# Estacion_meteo.net
KiCad netlist of a schematic drawn in EasyEDA
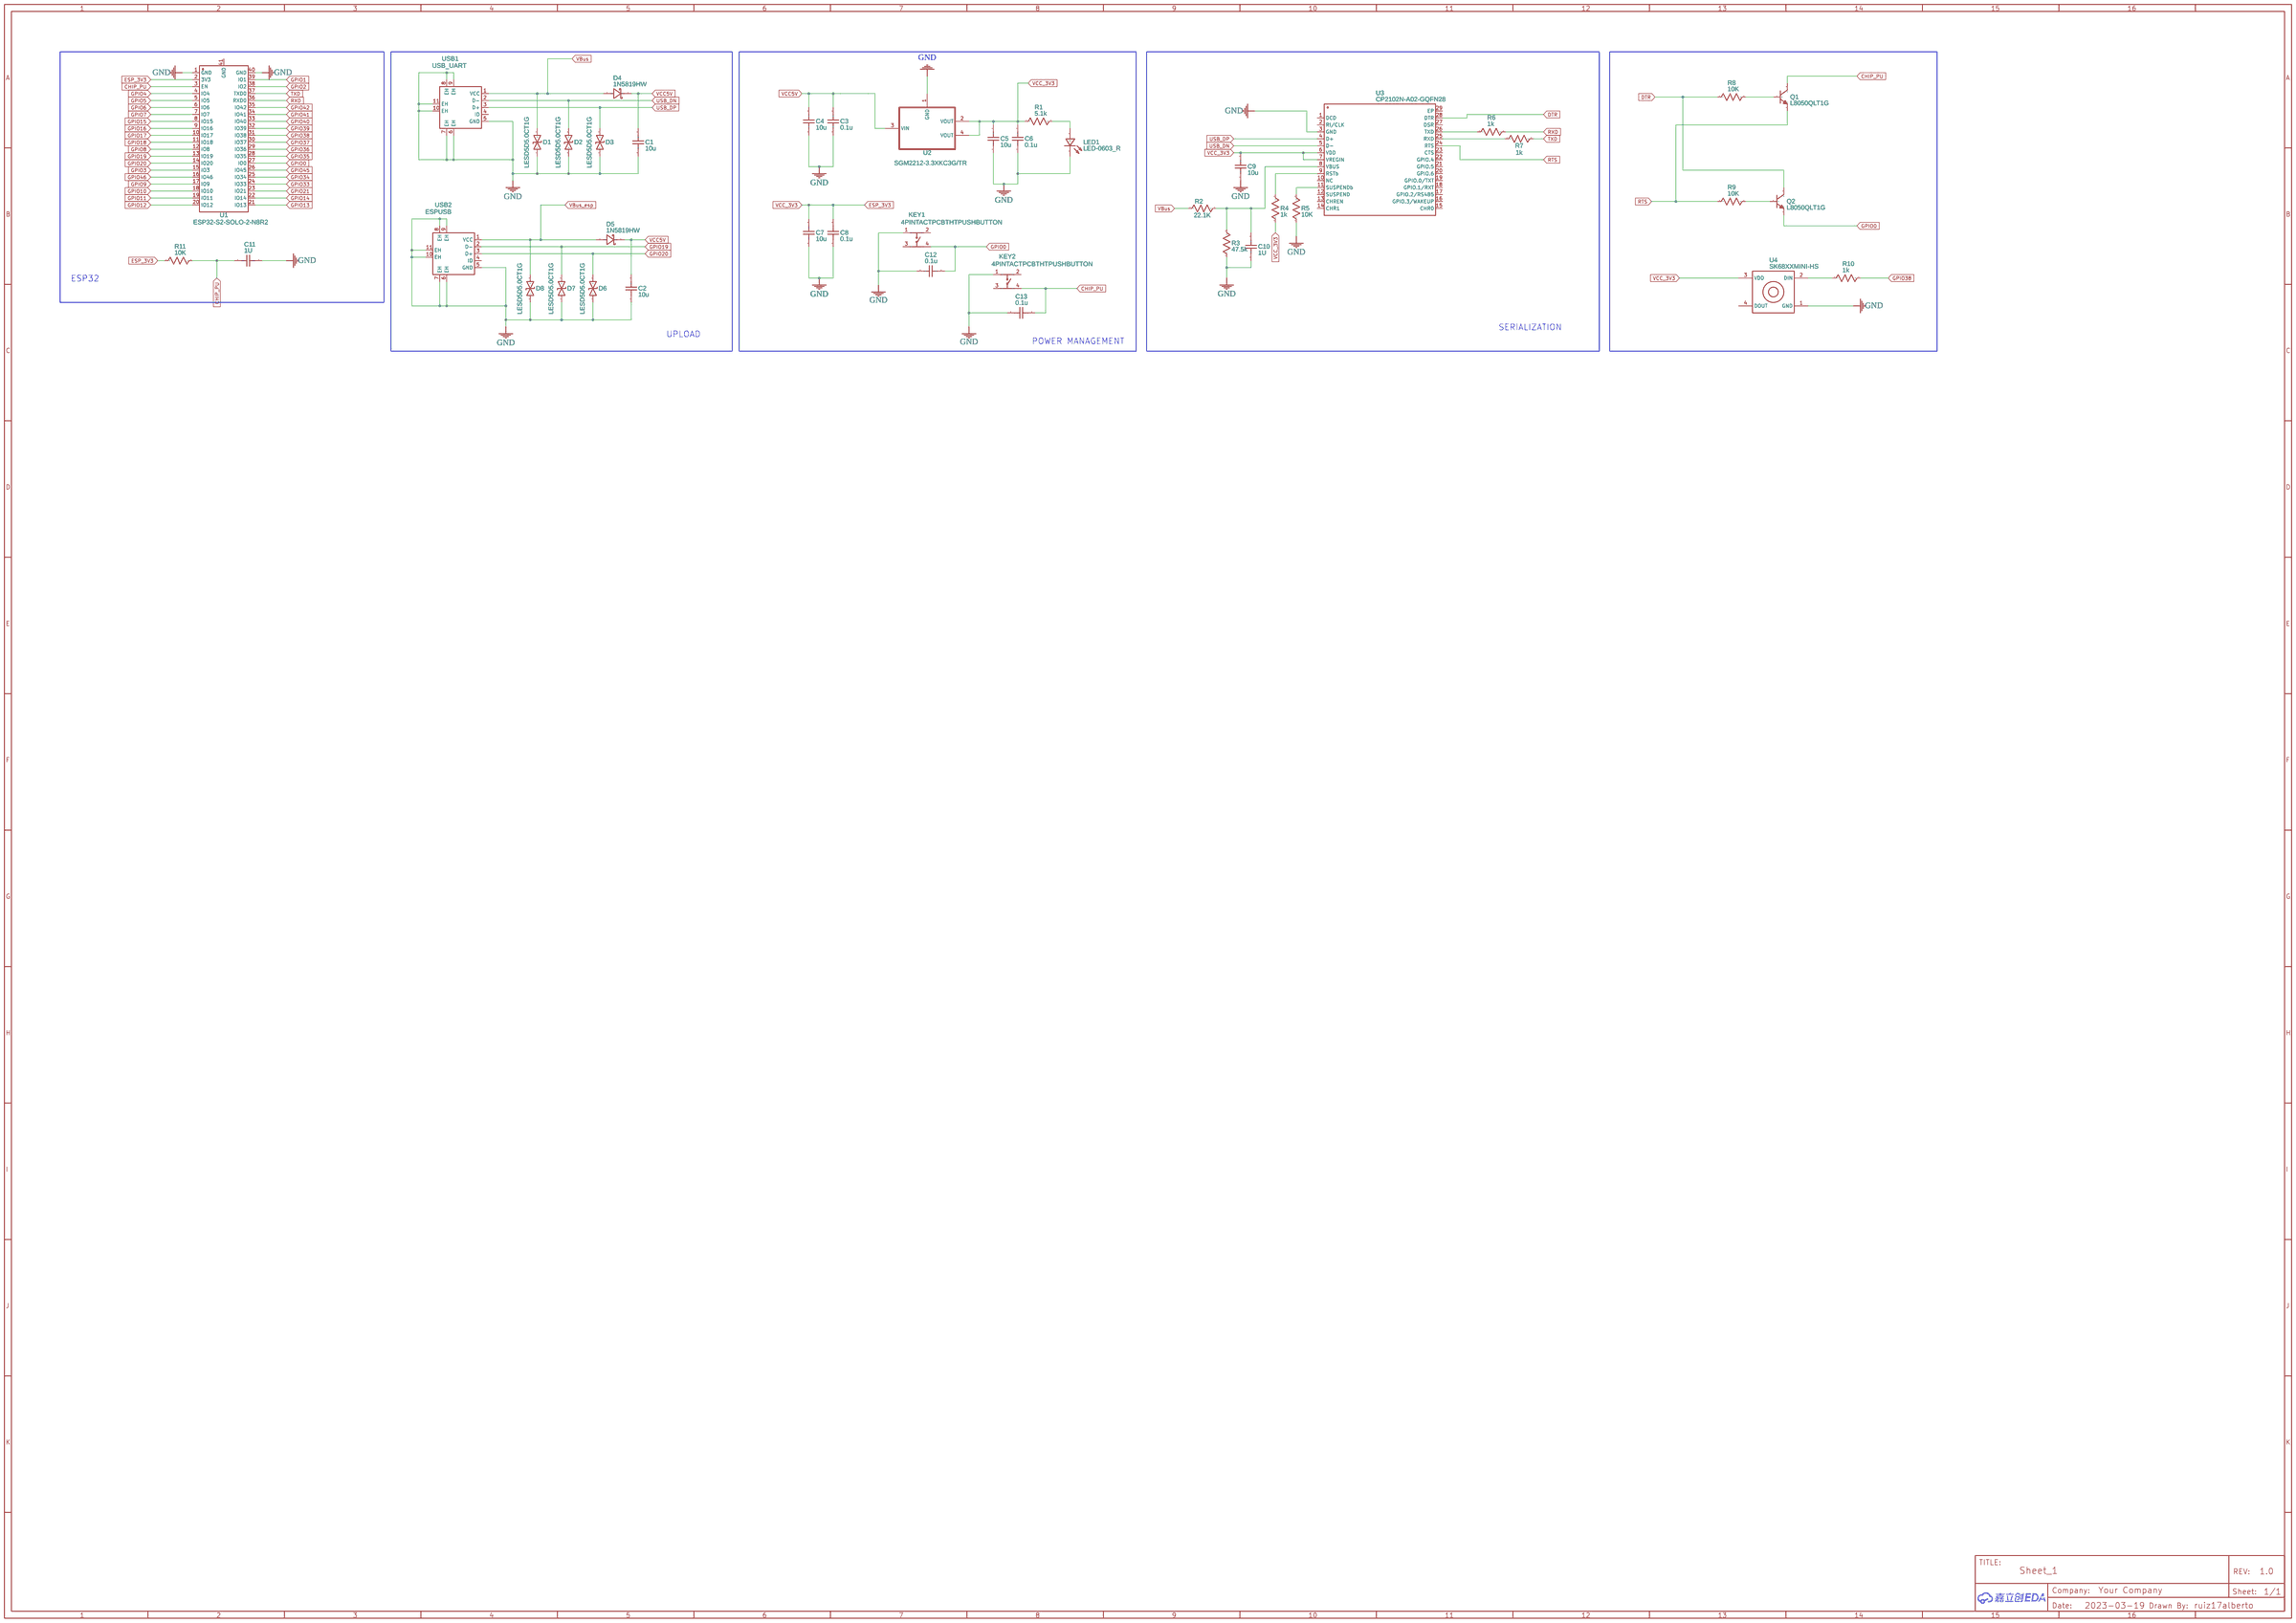
[diagram p0: schematic sheet]

(export (version "E")
  (design (tool "Eeschema 10.0.6"))
  (components
    (comp (ref "C1") (value "10u") (libsource (lib "") (part "C_0603_US")))
    (comp (ref "C2") (value "10u") (libsource (lib "") (part "C_0603_US")))
    (comp (ref "C3") (value "0.1u") (libsource (lib "") (part "C_0603_US")))
    (comp (ref "C4") (value "10u") (libsource (lib "") (part "C_0603_US")))
    (comp (ref "C5") (value "10u") (libsource (lib "") (part "C_0603_US")))
    (comp (ref "C6") (value "0.1u") (libsource (lib "") (part "C_0603_US")))
    (comp (ref "C7") (value "10u") (libsource (lib "") (part "C_0603_US")))
    (comp (ref "C8") (value "0.1u") (libsource (lib "") (part "C_0603_US")))
    (comp (ref "C9") (value "10u") (libsource (lib "") (part "C_0603_US")))
    (comp (ref "C10") (value "1U") (libsource (lib "") (part "C_0603_US")))
    (comp (ref "C11") (value "1U") (libsource (lib "") (part "C_0603_US_2")))
    (comp (ref "C12") (value "0.1u") (libsource (lib "") (part "C_0603_US_1")))
    (comp (ref "C13") (value "0.1u") (libsource (lib "") (part "C_0603_US_1")))
    (comp (ref "D1")
      (value "LESD5D5.0CT1G")
      (fields (field (name "Manufacturer") "LRC(乐山无线电)"))
      (libsource (lib "") (part "LESD5D5.0CT1G"))
    )
    (comp (ref "D2")
      (value "LESD5D5.0CT1G")
      (fields (field (name "Manufacturer") "LRC(乐山无线电)"))
      (libsource (lib "") (part "LESD5D5.0CT1G"))
    )
    (comp (ref "D3")
      (value "LESD5D5.0CT1G")
      (fields (field (name "Manufacturer") "LRC(乐山无线电)"))
      (libsource (lib "") (part "LESD5D5.0CT1G"))
    )
    (comp (ref "D4")
      (value "1N5819HW")
      (fields (field (name "Manufacturer") "TECH PUBLIC(台舟)"))
      (libsource (lib "") (part "1N5819HW"))
    )
    (comp (ref "D5")
      (value "1N5819HW")
      (fields (field (name "Manufacturer") "TECH PUBLIC(台舟)"))
      (libsource (lib "") (part "1N5819HW"))
    )
    (comp (ref "D6")
      (value "LESD5D5.0CT1G")
      (fields (field (name "Manufacturer") "LRC(乐山无线电)"))
      (libsource (lib "") (part "LESD5D5.0CT1G"))
    )
    (comp (ref "D7")
      (value "LESD5D5.0CT1G")
      (fields (field (name "Manufacturer") "LRC(乐山无线电)"))
      (libsource (lib "") (part "LESD5D5.0CT1G"))
    )
    (comp (ref "D8")
      (value "LESD5D5.0CT1G")
      (fields (field (name "Manufacturer") "LRC(乐山无线电)"))
      (libsource (lib "") (part "LESD5D5.0CT1G"))
    )
    (comp (ref "KEY1")
      (value "4PINTACTPCBTHTPUSHBUTTON")
      (fields (field (name "Manufacturer Part") "4pinTACTPCBTHTPushButton"))
      (libsource (lib "") (part "4PINTACTPCBTHTPUSHBUTTON"))
    )
    (comp (ref "KEY2")
      (value "4PINTACTPCBTHTPUSHBUTTON")
      (fields (field (name "Manufacturer Part") "4pinTACTPCBTHTPushButton"))
      (libsource (lib "") (part "4PINTACTPCBTHTPUSHBUTTON"))
    )
    (comp (ref "LED1")
      (value "LED-0603_R")
      (fields
        (field (name "BOM_Manufacturer Part") "19-217/R6C-AL1M2VY/3T")
        (field (name "BOM_Supplier Part") "C72044")
      )
      (libsource (lib "") (part "LED-0603_R"))
    )
    (comp (ref "Q1")
      (value "L8050QLT1G")
      (fields (field (name "Manufacturer") "LRC(乐山无线电)"))
      (libsource (lib "") (part "L8050QLT1G"))
    )
    (comp (ref "Q2")
      (value "L8050QLT1G")
      (fields (field (name "Manufacturer") "LRC(乐山无线电)"))
      (libsource (lib "") (part "L8050QLT1G"))
    )
    (comp (ref "R1") (value "5.1k") (libsource (lib "") (part "R_0603_US")))
    (comp (ref "R2") (value "22.1K") (libsource (lib "") (part "R_0603_US")))
    (comp (ref "R3") (value "47.5k") (libsource (lib "") (part "R_0603_US_1")))
    (comp (ref "R4") (value "1k") (libsource (lib "") (part "R_0603_US_1")))
    (comp (ref "R5") (value "10K") (libsource (lib "") (part "R_0603_US_1")))
    (comp (ref "R6") (value "1k") (libsource (lib "") (part "R_0603_US")))
    (comp (ref "R7") (value "1k") (libsource (lib "") (part "R_0603_US")))
    (comp (ref "R8") (value "10K") (libsource (lib "") (part "R_0603_US")))
    (comp (ref "R9") (value "10K") (libsource (lib "") (part "R_0603_US")))
    (comp (ref "R10") (value "1k") (libsource (lib "") (part "R_0603_US")))
    (comp (ref "R11") (value "10K") (libsource (lib "") (part "R_0603_US")))
    (comp (ref "U1") (value "ESP32-S2-SOLO-2-N8R2") (libsource (lib "") (part "ESP32-S2-SOLO-2-N8R2")))
    (comp (ref "U2") (value "SGM2212-3.3XKC3G/TR") (libsource (lib "") (part "SGM2212-3.3XKC3G/TR")))
    (comp (ref "U3")
      (value "CP2102N-A02-GQFN28")
      (fields (field (name "Manufacturer") "SKYWORKS/SILICON LABS(芯科)"))
      (libsource (lib "") (part "CP2102N-A02-GQFN28"))
    )
    (comp (ref "U4")
      (value "SK68XXMINI-HS")
      (fields (field (name "BOM_Supplier Part") "1528-1541-ND"))
      (libsource (lib "") (part "SK68XXMINI-HS"))
    )
    (comp (ref "USB1")
      (value "USB_UART")
      (fields (field (name "Manufacturer Part") "MICROUSB5S"))
      (libsource (lib "") (part "MICROUSB5S"))
    )
    (comp (ref "USB2")
      (value "ESPUSB")
      (fields (field (name "Manufacturer Part") "MICROUSB5S"))
      (libsource (lib "") (part "MICROUSB5S"))
    )
  )
  (nets
    (net (code "1") (name "CHIP_PU") (class "Default")
      (node (ref "C11") (pin "1") (pinfunction "1_1") (pintype "unspecified"))
      (node (ref "C13") (pin "1") (pinfunction "1_1") (pintype "unspecified"))
      (node (ref "KEY2") (pin "4") (pinfunction "4_4") (pintype "unspecified"))
      (node (ref "Q1") (pin "3") (pinfunction "C_3") (pintype "unspecified"))
      (node (ref "R11") (pin "2") (pinfunction "2_2") (pintype "unspecified"))
      (node (ref "U1") (pin "3") (pinfunction "EN_3") (pintype "unspecified"))
    )
    (net (code "2") (name "DTR") (class "Default")
      (node (ref "Q2") (pin "3") (pinfunction "C_3") (pintype "unspecified"))
      (node (ref "R8") (pin "1") (pinfunction "1_1") (pintype "unspecified"))
      (node (ref "U3") (pin "28") (pinfunction "DTR_28") (pintype "unspecified"))
    )
    (net (code "3") (name "ESP_3V3") (class "Default")
      (node (ref "C5") (pin "2") (pinfunction "2_2") (pintype "unspecified"))
      (node (ref "C6") (pin "2") (pinfunction "2_2") (pintype "unspecified"))
      (node (ref "C7") (pin "2") (pinfunction "2_2") (pintype "unspecified"))
      (node (ref "C8") (pin "2") (pinfunction "2_2") (pintype "unspecified"))
      (node (ref "C9") (pin "2") (pinfunction "2_2") (pintype "unspecified"))
      (node (ref "R1") (pin "1") (pinfunction "1_1") (pintype "unspecified"))
      (node (ref "R11") (pin "1") (pinfunction "1_1") (pintype "unspecified"))
      (node (ref "R4") (pin "1") (pinfunction "1_1") (pintype "unspecified"))
      (node (ref "U1") (pin "2") (pinfunction "3V3_2") (pintype "unspecified"))
      (node (ref "U2") (pin "2") (pinfunction "VOUT_2") (pintype "unspecified"))
      (node (ref "U2") (pin "4") (pinfunction "VOUT_4") (pintype "unspecified"))
      (node (ref "U3") (pin "6") (pinfunction "VDD_6") (pintype "unspecified"))
      (node (ref "U3") (pin "7") (pinfunction "VREGIN_7") (pintype "unspecified"))
      (node (ref "U4") (pin "3") (pinfunction "VDD_3") (pintype "unspecified"))
    )
    (net (code "4") (name "GND") (class "Default")
      (node (ref "C1") (pin "1") (pinfunction "1_1") (pintype "unspecified"))
      (node (ref "C10") (pin "1") (pinfunction "1_1") (pintype "unspecified"))
      (node (ref "C11") (pin "2") (pinfunction "2_2") (pintype "unspecified"))
      (node (ref "C12") (pin "2") (pinfunction "2_2") (pintype "unspecified"))
      (node (ref "C13") (pin "2") (pinfunction "2_2") (pintype "unspecified"))
      (node (ref "C2") (pin "1") (pinfunction "1_1") (pintype "unspecified"))
      (node (ref "C3") (pin "1") (pinfunction "1_1") (pintype "unspecified"))
      (node (ref "C4") (pin "1") (pinfunction "1_1") (pintype "unspecified"))
      (node (ref "C5") (pin "1") (pinfunction "1_1") (pintype "unspecified"))
      (node (ref "C6") (pin "1") (pinfunction "1_1") (pintype "unspecified"))
      (node (ref "C7") (pin "1") (pinfunction "1_1") (pintype "unspecified"))
      (node (ref "C8") (pin "1") (pinfunction "1_1") (pintype "unspecified"))
      (node (ref "C9") (pin "1") (pinfunction "1_1") (pintype "unspecified"))
      (node (ref "D1") (pin "1") (pinfunction "1_1") (pintype "unspecified"))
      (node (ref "D2") (pin "1") (pinfunction "1_1") (pintype "unspecified"))
      (node (ref "D3") (pin "1") (pinfunction "1_1") (pintype "unspecified"))
      (node (ref "D6") (pin "1") (pinfunction "1_1") (pintype "unspecified"))
      (node (ref "D7") (pin "1") (pinfunction "1_1") (pintype "unspecified"))
      (node (ref "D8") (pin "1") (pinfunction "1_1") (pintype "unspecified"))
      (node (ref "KEY1") (pin "1") (pinfunction "1_1") (pintype "unspecified"))
      (node (ref "KEY2") (pin "1") (pinfunction "1_1") (pintype "unspecified"))
      (node (ref "LED1") (pin "2") (pinfunction "2_2") (pintype "unspecified"))
      (node (ref "R3") (pin "1") (pinfunction "1_1") (pintype "unspecified"))
      (node (ref "R5") (pin "1") (pinfunction "1_1") (pintype "unspecified"))
      (node (ref "U1") (pin "1") (pinfunction "GND_1") (pintype "unspecified"))
      (node (ref "U1") (pin "40") (pinfunction "GND_40") (pintype "unspecified"))
      (node (ref "U2") (pin "1") (pinfunction "GND_1") (pintype "unspecified"))
      (node (ref "U3") (pin "3") (pinfunction "GND_3") (pintype "unspecified"))
      (node (ref "U4") (pin "1") (pinfunction "GND_1") (pintype "unspecified"))
      (node (ref "USB1") (pin "10") (pinfunction "EH_10") (pintype "unspecified"))
      (node (ref "USB1") (pin "11") (pinfunction "EH_11") (pintype "unspecified"))
      (node (ref "USB1") (pin "5") (pinfunction "GND_5") (pintype "input"))
      (node (ref "USB1") (pin "6") (pinfunction "EH_6") (pintype "unspecified"))
      (node (ref "USB1") (pin "7") (pinfunction "EH_7") (pintype "unspecified"))
      (node (ref "USB1") (pin "8") (pinfunction "EH_8") (pintype "unspecified"))
      (node (ref "USB1") (pin "9") (pinfunction "EH_9") (pintype "unspecified"))
      (node (ref "USB2") (pin "10") (pinfunction "EH_10") (pintype "unspecified"))
      (node (ref "USB2") (pin "11") (pinfunction "EH_11") (pintype "unspecified"))
      (node (ref "USB2") (pin "5") (pinfunction "GND_5") (pintype "input"))
      (node (ref "USB2") (pin "6") (pinfunction "EH_6") (pintype "unspecified"))
      (node (ref "USB2") (pin "7") (pinfunction "EH_7") (pintype "unspecified"))
      (node (ref "USB2") (pin "8") (pinfunction "EH_8") (pintype "unspecified"))
      (node (ref "USB2") (pin "9") (pinfunction "EH_9") (pintype "unspecified"))
    )
    (net (code "5") (name "GPIO0") (class "Default")
      (node (ref "C12") (pin "1") (pinfunction "1_1") (pintype "unspecified"))
      (node (ref "KEY1") (pin "4") (pinfunction "4_4") (pintype "unspecified"))
      (node (ref "Q2") (pin "2") (pinfunction "E_2") (pintype "unspecified"))
      (node (ref "U1") (pin "27") (pinfunction "IO0_27") (pintype "unspecified"))
    )
    (net (code "6") (name "GPIO1") (class "Default")
      (node (ref "U1") (pin "39") (pinfunction "IO1_39") (pintype "unspecified"))
    )
    (net (code "7") (name "GPIO2") (class "Default")
      (node (ref "U1") (pin "38") (pinfunction "IO2_38") (pintype "unspecified"))
    )
    (net (code "8") (name "GPIO3") (class "Default")
      (node (ref "U1") (pin "15") (pinfunction "IO3_15") (pintype "unspecified"))
    )
    (net (code "9") (name "GPIO4") (class "Default")
      (node (ref "U1") (pin "4") (pinfunction "IO4_4") (pintype "unspecified"))
    )
    (net (code "10") (name "GPIO5") (class "Default")
      (node (ref "U1") (pin "5") (pinfunction "IO5_5") (pintype "unspecified"))
    )
    (net (code "11") (name "GPIO6") (class "Default")
      (node (ref "U1") (pin "6") (pinfunction "IO6_6") (pintype "unspecified"))
    )
    (net (code "12") (name "GPIO7") (class "Default")
      (node (ref "U1") (pin "7") (pinfunction "IO7_7") (pintype "unspecified"))
    )
    (net (code "13") (name "GPIO8") (class "Default")
      (node (ref "U1") (pin "12") (pinfunction "IO8_12") (pintype "unspecified"))
    )
    (net (code "14") (name "GPIO9") (class "Default")
      (node (ref "U1") (pin "17") (pinfunction "IO9_17") (pintype "unspecified"))
    )
    (net (code "15") (name "GPIO10") (class "Default")
      (node (ref "U1") (pin "18") (pinfunction "IO10_18") (pintype "unspecified"))
    )
    (net (code "16") (name "GPIO11") (class "Default")
      (node (ref "U1") (pin "19") (pinfunction "IO11_19") (pintype "unspecified"))
    )
    (net (code "17") (name "GPIO12") (class "Default")
      (node (ref "U1") (pin "20") (pinfunction "IO12_20") (pintype "unspecified"))
    )
    (net (code "18") (name "GPIO13") (class "Default")
      (node (ref "U1") (pin "21") (pinfunction "IO13_21") (pintype "unspecified"))
    )
    (net (code "19") (name "GPIO14") (class "Default")
      (node (ref "U1") (pin "22") (pinfunction "IO14_22") (pintype "unspecified"))
    )
    (net (code "20") (name "GPIO15") (class "Default")
      (node (ref "U1") (pin "8") (pinfunction "IO15_8") (pintype "unspecified"))
    )
    (net (code "21") (name "GPIO16") (class "Default")
      (node (ref "U1") (pin "9") (pinfunction "IO16_9") (pintype "unspecified"))
    )
    (net (code "22") (name "GPIO17") (class "Default")
      (node (ref "U1") (pin "10") (pinfunction "IO17_10") (pintype "unspecified"))
    )
    (net (code "23") (name "GPIO18") (class "Default")
      (node (ref "U1") (pin "11") (pinfunction "IO18_11") (pintype "unspecified"))
    )
    (net (code "24") (name "GPIO19") (class "Default")
      (node (ref "D7") (pin "2") (pinfunction "2_2") (pintype "unspecified"))
      (node (ref "U1") (pin "13") (pinfunction "IO19_13") (pintype "unspecified"))
      (node (ref "USB2") (pin "2") (pinfunction "D-_2") (pintype "input"))
    )
    (net (code "25") (name "GPIO20") (class "Default")
      (node (ref "D6") (pin "2") (pinfunction "2_2") (pintype "unspecified"))
      (node (ref "U1") (pin "14") (pinfunction "IO20_14") (pintype "unspecified"))
      (node (ref "USB2") (pin "3") (pinfunction "D+_3") (pintype "input"))
    )
    (net (code "26") (name "GPIO21") (class "Default")
      (node (ref "U1") (pin "23") (pinfunction "IO21_23") (pintype "unspecified"))
    )
    (net (code "27") (name "GPIO33") (class "Default")
      (node (ref "U1") (pin "24") (pinfunction "IO33_24") (pintype "unspecified"))
    )
    (net (code "28") (name "GPIO34") (class "Default")
      (node (ref "U1") (pin "25") (pinfunction "IO34_25") (pintype "unspecified"))
    )
    (net (code "29") (name "GPIO35") (class "Default")
      (node (ref "U1") (pin "28") (pinfunction "IO35_28") (pintype "unspecified"))
    )
    (net (code "30") (name "GPIO36") (class "Default")
      (node (ref "U1") (pin "29") (pinfunction "IO36_29") (pintype "unspecified"))
    )
    (net (code "31") (name "GPIO37") (class "Default")
      (node (ref "U1") (pin "30") (pinfunction "IO37_30") (pintype "unspecified"))
    )
    (net (code "32") (name "GPIO38") (class "Default")
      (node (ref "R10") (pin "2") (pinfunction "2_2") (pintype "unspecified"))
      (node (ref "U1") (pin "31") (pinfunction "IO38_31") (pintype "unspecified"))
    )
    (net (code "33") (name "GPIO39") (class "Default")
      (node (ref "U1") (pin "32") (pinfunction "IO39_32") (pintype "unspecified"))
    )
    (net (code "34") (name "GPIO40") (class "Default")
      (node (ref "U1") (pin "33") (pinfunction "IO40_33") (pintype "unspecified"))
    )
    (net (code "35") (name "GPIO41") (class "Default")
      (node (ref "U1") (pin "34") (pinfunction "IO41_34") (pintype "unspecified"))
    )
    (net (code "36") (name "GPIO42") (class "Default")
      (node (ref "U1") (pin "35") (pinfunction "IO42_35") (pintype "unspecified"))
    )
    (net (code "37") (name "GPIO45") (class "Default")
      (node (ref "U1") (pin "26") (pinfunction "IO45_26") (pintype "unspecified"))
    )
    (net (code "38") (name "GPIO46") (class "Default")
      (node (ref "U1") (pin "16") (pinfunction "IO46_16") (pintype "unspecified"))
    )
    (net (code "39") (name "Net-(LED1-Pad1)") (class "Default")
      (node (ref "LED1") (pin "1") (pinfunction "1_1") (pintype "unspecified"))
      (node (ref "R1") (pin "2") (pinfunction "2_2") (pintype "unspecified"))
    )
    (net (code "40") (name "Net-(Q1-B)") (class "Default")
      (node (ref "Q1") (pin "1") (pinfunction "B_1") (pintype "unspecified"))
      (node (ref "R8") (pin "2") (pinfunction "2_2") (pintype "unspecified"))
    )
    (net (code "41") (name "Net-(Q2-B)") (class "Default")
      (node (ref "Q2") (pin "1") (pinfunction "B_1") (pintype "unspecified"))
      (node (ref "R9") (pin "2") (pinfunction "2_2") (pintype "unspecified"))
    )
    (net (code "42") (name "Net-(U3-RSTb)") (class "Default")
      (node (ref "R4") (pin "2") (pinfunction "2_2") (pintype "unspecified"))
      (node (ref "U3") (pin "9") (pinfunction "RSTb_9") (pintype "unspecified"))
    )
    (net (code "43") (name "Net-(U3-RXD)") (class "Default")
      (node (ref "R7") (pin "1") (pinfunction "1_1") (pintype "unspecified"))
      (node (ref "U3") (pin "25") (pinfunction "RXD_25") (pintype "unspecified"))
    )
    (net (code "44") (name "Net-(U3-SUSPENDb)") (class "Default")
      (node (ref "R5") (pin "2") (pinfunction "2_2") (pintype "unspecified"))
      (node (ref "U3") (pin "11") (pinfunction "SUSPENDb_11") (pintype "unspecified"))
    )
    (net (code "45") (name "Net-(U3-TXD)") (class "Default")
      (node (ref "R6") (pin "1") (pinfunction "1_1") (pintype "unspecified"))
      (node (ref "U3") (pin "26") (pinfunction "TXD_26") (pintype "unspecified"))
    )
    (net (code "46") (name "Net-(U3-VBUS)") (class "Default")
      (node (ref "C10") (pin "2") (pinfunction "2_2") (pintype "unspecified"))
      (node (ref "R2") (pin "2") (pinfunction "2_2") (pintype "unspecified"))
      (node (ref "R3") (pin "2") (pinfunction "2_2") (pintype "unspecified"))
      (node (ref "U3") (pin "8") (pinfunction "VBUS_8") (pintype "unspecified"))
    )
    (net (code "47") (name "Net-(U4-DIN)") (class "Default")
      (node (ref "R10") (pin "1") (pinfunction "1_1") (pintype "unspecified"))
      (node (ref "U4") (pin "2") (pinfunction "DIN_2") (pintype "unspecified"))
    )
    (net (code "48") (name "RTS") (class "Default")
      (node (ref "Q1") (pin "2") (pinfunction "E_2") (pintype "unspecified"))
      (node (ref "R9") (pin "1") (pinfunction "1_1") (pintype "unspecified"))
      (node (ref "U3") (pin "24") (pinfunction "RTS_24") (pintype "unspecified"))
    )
    (net (code "49") (name "RXD") (class "Default")
      (node (ref "R6") (pin "2") (pinfunction "2_2") (pintype "unspecified"))
      (node (ref "U1") (pin "36") (pinfunction "RXD0_36") (pintype "unspecified"))
    )
    (net (code "50") (name "TXD") (class "Default")
      (node (ref "R7") (pin "2") (pinfunction "2_2") (pintype "unspecified"))
      (node (ref "U1") (pin "37") (pinfunction "TXD0_37") (pintype "unspecified"))
    )
    (net (code "51") (name "USB_DN") (class "Default")
      (node (ref "D2") (pin "2") (pinfunction "2_2") (pintype "unspecified"))
      (node (ref "U3") (pin "5") (pinfunction "D-_5") (pintype "unspecified"))
      (node (ref "USB1") (pin "2") (pinfunction "D-_2") (pintype "input"))
    )
    (net (code "52") (name "USB_DP") (class "Default")
      (node (ref "D3") (pin "2") (pinfunction "2_2") (pintype "unspecified"))
      (node (ref "U3") (pin "4") (pinfunction "D+_4") (pintype "unspecified"))
      (node (ref "USB1") (pin "3") (pinfunction "D+_3") (pintype "input"))
    )
    (net (code "53") (name "VBus") (class "Default")
      (node (ref "D1") (pin "2") (pinfunction "2_2") (pintype "unspecified"))
      (node (ref "D4") (pin "2") (pinfunction "A_2") (pintype "unspecified"))
      (node (ref "R2") (pin "1") (pinfunction "1_1") (pintype "unspecified"))
      (node (ref "USB1") (pin "1") (pinfunction "VCC_1") (pintype "input"))
    )
    (net (code "54") (name "VBus_esp") (class "Default")
      (node (ref "D5") (pin "2") (pinfunction "A_2") (pintype "unspecified"))
      (node (ref "D8") (pin "2") (pinfunction "2_2") (pintype "unspecified"))
      (node (ref "USB2") (pin "1") (pinfunction "VCC_1") (pintype "input"))
    )
    (net (code "55") (name "VCC5V") (class "Default")
      (node (ref "C1") (pin "2") (pinfunction "2_2") (pintype "unspecified"))
      (node (ref "C2") (pin "2") (pinfunction "2_2") (pintype "unspecified"))
      (node (ref "C3") (pin "2") (pinfunction "2_2") (pintype "unspecified"))
      (node (ref "C4") (pin "2") (pinfunction "2_2") (pintype "unspecified"))
      (node (ref "D4") (pin "1") (pinfunction "K_1") (pintype "unspecified"))
      (node (ref "D5") (pin "1") (pinfunction "K_1") (pintype "unspecified"))
      (node (ref "U2") (pin "3") (pinfunction "VIN_3") (pintype "unspecified"))
    )
    (net (code "56") (name "unconnected-(KEY1-Pad2)") (class "Default")
      (node (ref "KEY1") (pin "2") (pinfunction "2_2") (pintype "unspecified"))
    )
    (net (code "57") (name "unconnected-(KEY1-Pad3)") (class "Default")
      (node (ref "KEY1") (pin "3") (pinfunction "3_3") (pintype "unspecified"))
    )
    (net (code "58") (name "unconnected-(KEY2-Pad2)") (class "Default")
      (node (ref "KEY2") (pin "2") (pinfunction "2_2") (pintype "unspecified"))
    )
    (net (code "59") (name "unconnected-(KEY2-Pad3)") (class "Default")
      (node (ref "KEY2") (pin "3") (pinfunction "3_3") (pintype "unspecified"))
    )
    (net (code "60") (name "unconnected-(U1-GND-Pad41)") (class "Default")
      (node (ref "U1") (pin "41") (pinfunction "GND_41") (pintype "unspecified"))
    )
    (net (code "61") (name "unconnected-(U3-CHR0-Pad15)") (class "Default")
      (node (ref "U3") (pin "15") (pinfunction "CHR0_15") (pintype "unspecified"))
    )
    (net (code "62") (name "unconnected-(U3-CHR1-Pad14)") (class "Default")
      (node (ref "U3") (pin "14") (pinfunction "CHR1_14") (pintype "unspecified"))
    )
    (net (code "63") (name "unconnected-(U3-CHREN-Pad13)") (class "Default")
      (node (ref "U3") (pin "13") (pinfunction "CHREN_13") (pintype "unspecified"))
    )
    (net (code "64") (name "unconnected-(U3-CTS-Pad23)") (class "Default")
      (node (ref "U3") (pin "23") (pinfunction "CTS_23") (pintype "unspecified"))
    )
    (net (code "65") (name "unconnected-(U3-DCD-Pad1)") (class "Default")
      (node (ref "U3") (pin "1") (pinfunction "DCD_1") (pintype "unspecified"))
    )
    (net (code "66") (name "unconnected-(U3-DSR-Pad27)") (class "Default")
      (node (ref "U3") (pin "27") (pinfunction "DSR_27") (pintype "unspecified"))
    )
    (net (code "67") (name "unconnected-(U3-EP-Pad29)") (class "Default")
      (node (ref "U3") (pin "29") (pinfunction "EP_29") (pintype "unspecified"))
    )
    (net (code "68") (name "unconnected-(U3-GPIO.0{slash}TXT-Pad19)") (class "Default")
      (node (ref "U3") (pin "19") (pinfunction "GPIO.0/TXT_19") (pintype "unspecified"))
    )
    (net (code "69") (name "unconnected-(U3-GPIO.1{slash}RXT-Pad18)") (class "Default")
      (node (ref "U3") (pin "18") (pinfunction "GPIO.1/RXT_18") (pintype "unspecified"))
    )
    (net (code "70") (name "unconnected-(U3-GPIO.2{slash}RS485-Pad17)") (class "Default")
      (node (ref "U3") (pin "17") (pinfunction "GPIO.2/RS485_17") (pintype "unspecified"))
    )
    (net (code "71") (name "unconnected-(U3-GPIO.3{slash}WAKEUP-Pad16)") (class "Default")
      (node (ref "U3") (pin "16") (pinfunction "GPIO.3/WAKEUP_16") (pintype "unspecified"))
    )
    (net (code "72") (name "unconnected-(U3-GPIO.4-Pad22)") (class "Default")
      (node (ref "U3") (pin "22") (pinfunction "GPIO.4_22") (pintype "unspecified"))
    )
    (net (code "73") (name "unconnected-(U3-GPIO.5-Pad21)") (class "Default")
      (node (ref "U3") (pin "21") (pinfunction "GPIO.5_21") (pintype "unspecified"))
    )
    (net (code "74") (name "unconnected-(U3-GPIO.6-Pad20)") (class "Default")
      (node (ref "U3") (pin "20") (pinfunction "GPIO.6_20") (pintype "unspecified"))
    )
    (net (code "75") (name "unconnected-(U3-NC-Pad10)") (class "Default")
      (node (ref "U3") (pin "10") (pinfunction "NC_10") (pintype "unspecified"))
    )
    (net (code "76") (name "unconnected-(U3-RI{slash}CLK-Pad2)") (class "Default")
      (node (ref "U3") (pin "2") (pinfunction "RI/CLK_2") (pintype "unspecified"))
    )
    (net (code "77") (name "unconnected-(U3-SUSPEND-Pad12)") (class "Default")
      (node (ref "U3") (pin "12") (pinfunction "SUSPEND_12") (pintype "unspecified"))
    )
    (net (code "78") (name "unconnected-(U4-DOUT-Pad4)") (class "Default")
      (node (ref "U4") (pin "4") (pinfunction "DOUT_4") (pintype "unspecified"))
    )
    (net (code "79") (name "unconnected-(USB1-ID-Pad4)") (class "Default")
      (node (ref "USB1") (pin "4") (pinfunction "ID_4") (pintype "input"))
    )
    (net (code "80") (name "unconnected-(USB2-ID-Pad4)") (class "Default")
      (node (ref "USB2") (pin "4") (pinfunction "ID_4") (pintype "input"))
    )
  )
)
